# car_plot.net
KiCad netlist of a schematic drawn in EasyEDA
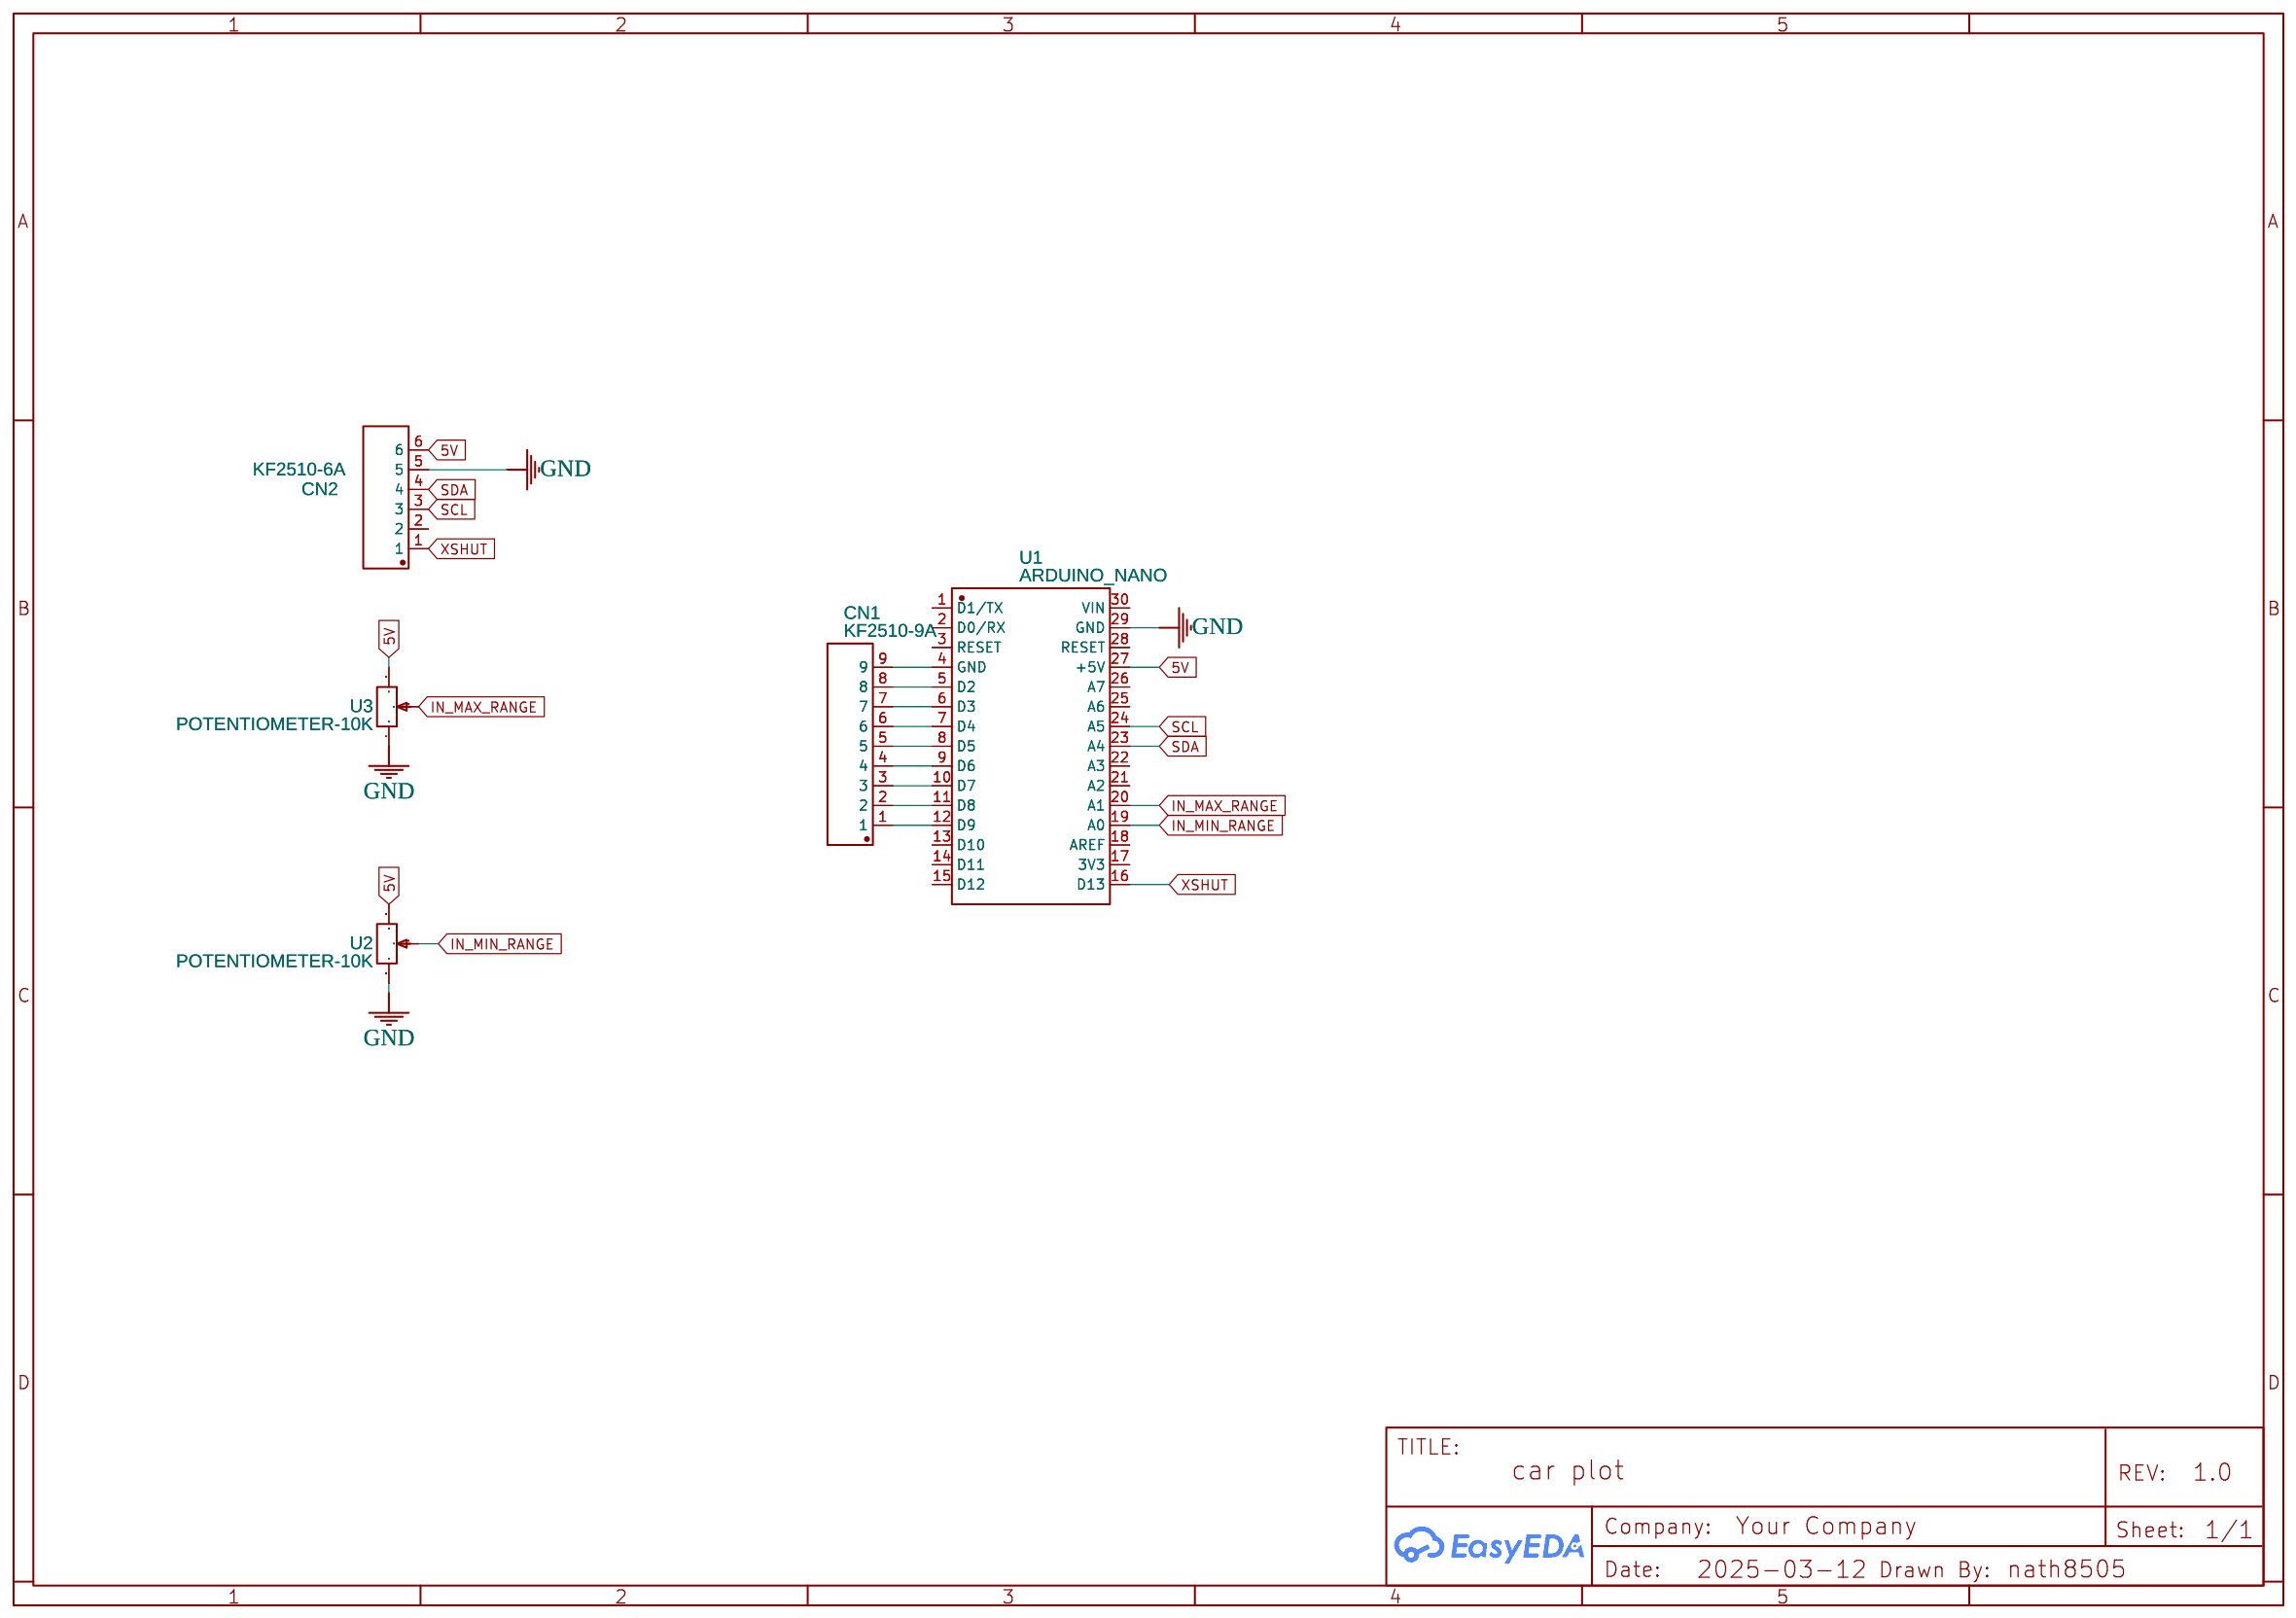
[diagram p0: schematic sheet]

(export (version "E")
  (design (tool "Eeschema 10.0.6"))
  (components
    (comp (ref "CN1")
      (value "KF2510-9A")
      (fields (field (name "Manufacturer Part") "2510-9A") (field (name "Manufacturer") "BOOMELE(博穆精密)"))
      (libsource (lib "") (part "KF2510-9A"))
    )
    (comp (ref "CN2")
      (value "KF2510-6A")
      (fields (field (name "Manufacturer Part") "KF2510-6A针座"))
      (libsource (lib "") (part "KF2510-6A"))
    )
    (comp (ref "U1") (value "ARDUINO_NANO") (libsource (lib "") (part "ARDUINO_NANO")))
    (comp (ref "U2")
      (value "POTENTIOMETER-10K")
      (fields (field (name "Manufacturer Part") "3*3Potentiometer-10kΩ20%"))
      (libsource (lib "") (part "3*3POTENTIOMETER-10KΩ20%"))
    )
    (comp (ref "U3")
      (value "POTENTIOMETER-10K")
      (fields (field (name "Manufacturer Part") "3*3Potentiometer-10kΩ20%"))
      (libsource (lib "") (part "3*3POTENTIOMETER-10KΩ20%"))
    )
  )
  (nets
    (net (code "1") (name "5V") (class "Default")
      (node (ref "CN2") (pin "6") (pinfunction "6_6") (pintype "unspecified"))
      (node (ref "U1") (pin "27") (pinfunction "+5V_27") (pintype "unspecified"))
      (node (ref "U2") (pin "3") (pinfunction "3_3") (pintype "input"))
      (node (ref "U3") (pin "3") (pinfunction "3_3") (pintype "input"))
    )
    (net (code "2") (name "GND") (class "Default")
      (node (ref "CN2") (pin "5") (pinfunction "5_5") (pintype "unspecified"))
      (node (ref "U1") (pin "29") (pinfunction "GND_29") (pintype "unspecified"))
      (node (ref "U2") (pin "1") (pinfunction "1_1") (pintype "input"))
      (node (ref "U3") (pin "1") (pinfunction "1_1") (pintype "input"))
    )
    (net (code "3") (name "IN_MAX_RANGE") (class "Default")
      (node (ref "U1") (pin "20") (pinfunction "A1_20") (pintype "unspecified"))
      (node (ref "U3") (pin "2") (pinfunction "2_2") (pintype "input"))
    )
    (net (code "4") (name "IN_MIN_RANGE") (class "Default")
      (node (ref "U1") (pin "19") (pinfunction "A0_19") (pintype "unspecified"))
      (node (ref "U2") (pin "2") (pinfunction "2_2") (pintype "input"))
    )
    (net (code "5") (name "Net-(CN1-Pad9)") (class "Default")
      (node (ref "CN1") (pin "9") (pinfunction "9_9") (pintype "unspecified"))
      (node (ref "U1") (pin "4") (pinfunction "GND_4") (pintype "unspecified"))
    )
    (net (code "6") (name "Net-(U1-D2)") (class "Default")
      (node (ref "CN1") (pin "8") (pinfunction "8_8") (pintype "unspecified"))
      (node (ref "U1") (pin "5") (pinfunction "D2_5") (pintype "unspecified"))
    )
    (net (code "7") (name "Net-(U1-D3)") (class "Default")
      (node (ref "CN1") (pin "7") (pinfunction "7_7") (pintype "unspecified"))
      (node (ref "U1") (pin "6") (pinfunction "D3_6") (pintype "unspecified"))
    )
    (net (code "8") (name "Net-(U1-D4)") (class "Default")
      (node (ref "CN1") (pin "6") (pinfunction "6_6") (pintype "unspecified"))
      (node (ref "U1") (pin "7") (pinfunction "D4_7") (pintype "unspecified"))
    )
    (net (code "9") (name "Net-(U1-D5)") (class "Default")
      (node (ref "CN1") (pin "5") (pinfunction "5_5") (pintype "unspecified"))
      (node (ref "U1") (pin "8") (pinfunction "D5_8") (pintype "unspecified"))
    )
    (net (code "10") (name "Net-(U1-D6)") (class "Default")
      (node (ref "CN1") (pin "4") (pinfunction "4_4") (pintype "unspecified"))
      (node (ref "U1") (pin "9") (pinfunction "D6_9") (pintype "unspecified"))
    )
    (net (code "11") (name "Net-(U1-D7)") (class "Default")
      (node (ref "CN1") (pin "3") (pinfunction "3_3") (pintype "unspecified"))
      (node (ref "U1") (pin "10") (pinfunction "D7_10") (pintype "unspecified"))
    )
    (net (code "12") (name "Net-(U1-D8)") (class "Default")
      (node (ref "CN1") (pin "2") (pinfunction "2_2") (pintype "unspecified"))
      (node (ref "U1") (pin "11") (pinfunction "D8_11") (pintype "unspecified"))
    )
    (net (code "13") (name "Net-(U1-D9)") (class "Default")
      (node (ref "CN1") (pin "1") (pinfunction "1_1") (pintype "unspecified"))
      (node (ref "U1") (pin "12") (pinfunction "D9_12") (pintype "unspecified"))
    )
    (net (code "14") (name "SCL") (class "Default")
      (node (ref "CN2") (pin "3") (pinfunction "3_3") (pintype "unspecified"))
      (node (ref "U1") (pin "24") (pinfunction "A5_24") (pintype "unspecified"))
    )
    (net (code "15") (name "SDA") (class "Default")
      (node (ref "CN2") (pin "4") (pinfunction "4_4") (pintype "unspecified"))
      (node (ref "U1") (pin "23") (pinfunction "A4_23") (pintype "unspecified"))
    )
    (net (code "16") (name "XSHUT") (class "Default")
      (node (ref "CN2") (pin "1") (pinfunction "1_1") (pintype "unspecified"))
      (node (ref "U1") (pin "16") (pinfunction "D13_16") (pintype "unspecified"))
    )
    (net (code "17") (name "unconnected-(CN2-Pad2)") (class "Default")
      (node (ref "CN2") (pin "2") (pinfunction "2_2") (pintype "unspecified"))
    )
    (net (code "18") (name "unconnected-(U1-3V3-Pad17)") (class "Default")
      (node (ref "U1") (pin "17") (pinfunction "3V3_17") (pintype "unspecified"))
    )
    (net (code "19") (name "unconnected-(U1-A2-Pad21)") (class "Default")
      (node (ref "U1") (pin "21") (pinfunction "A2_21") (pintype "unspecified"))
    )
    (net (code "20") (name "unconnected-(U1-A3-Pad22)") (class "Default")
      (node (ref "U1") (pin "22") (pinfunction "A3_22") (pintype "unspecified"))
    )
    (net (code "21") (name "unconnected-(U1-A6-Pad25)") (class "Default")
      (node (ref "U1") (pin "25") (pinfunction "A6_25") (pintype "unspecified"))
    )
    (net (code "22") (name "unconnected-(U1-A7-Pad26)") (class "Default")
      (node (ref "U1") (pin "26") (pinfunction "A7_26") (pintype "unspecified"))
    )
    (net (code "23") (name "unconnected-(U1-AREF-Pad18)") (class "Default")
      (node (ref "U1") (pin "18") (pinfunction "AREF_18") (pintype "unspecified"))
    )
    (net (code "24") (name "unconnected-(U1-D0{slash}RX-Pad2)") (class "Default")
      (node (ref "U1") (pin "2") (pinfunction "D0/RX_2") (pintype "unspecified"))
    )
    (net (code "25") (name "unconnected-(U1-D1{slash}TX-Pad1)") (class "Default")
      (node (ref "U1") (pin "1") (pinfunction "D1/TX_1") (pintype "unspecified"))
    )
    (net (code "26") (name "unconnected-(U1-D10-Pad13)") (class "Default")
      (node (ref "U1") (pin "13") (pinfunction "D10_13") (pintype "unspecified"))
    )
    (net (code "27") (name "unconnected-(U1-D11-Pad14)") (class "Default")
      (node (ref "U1") (pin "14") (pinfunction "D11_14") (pintype "unspecified"))
    )
    (net (code "28") (name "unconnected-(U1-D12-Pad15)") (class "Default")
      (node (ref "U1") (pin "15") (pinfunction "D12_15") (pintype "unspecified"))
    )
    (net (code "29") (name "unconnected-(U1-RESET-Pad3)") (class "Default")
      (node (ref "U1") (pin "3") (pinfunction "RESET_3") (pintype "unspecified"))
    )
    (net (code "30") (name "unconnected-(U1-RESET-Pad28)") (class "Default")
      (node (ref "U1") (pin "28") (pinfunction "RESET_28") (pintype "unspecified"))
    )
    (net (code "31") (name "unconnected-(U1-VIN-Pad30)") (class "Default")
      (node (ref "U1") (pin "30") (pinfunction "VIN_30") (pintype "unspecified"))
    )
  )
)
